# EPS_Local-Supply_Channel.net
KiCad netlist of a schematic drawn in Altium Designer
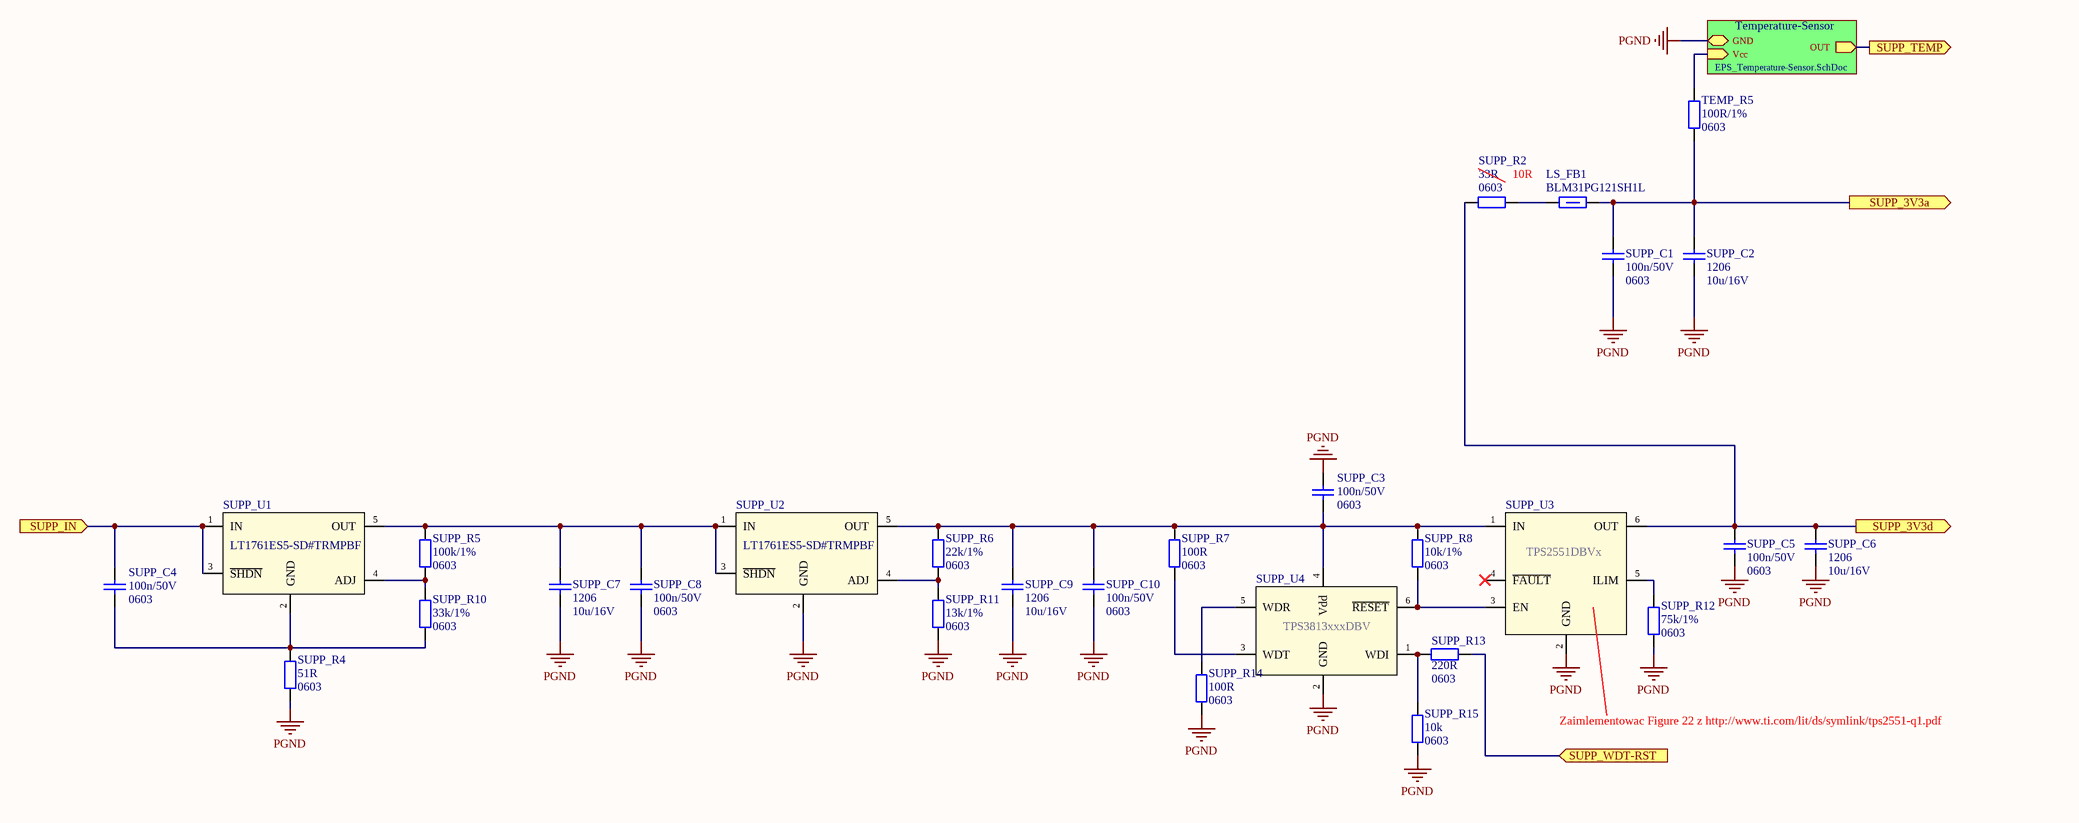
[diagram p0: EPS_Local-Supply_Channel.SchDoc]

(export (version "E")
  (design (tool "Eeschema 10.0.6"))
  (components
    (comp (ref "LS_FB1")
      (value "120R/100MHz")
      (footprint "SMD_FerriteBead_1206")
      (description "Ferrite bead, 1206, 0.02HM, 3.5A.")
      (fields (field (name "MANUFACTURER") "Murata") (field (name "MANUFACTURERPARTNUMBER") "BLM31PG121SH1L"))
      (libsource (lib "inductors") (part "BLM31PG121SH1L"))
    )
    (comp (ref "SUPP_C1")
      (value "100n/50V")
      (footprint "SMD_Capacitor_0603")
      (description "Ceramic Cap Kemet COTS 100n/50V X7R 0603")
      (fields
        (field (name "MANUFACTURER") "Kemet")
        (field (name "MANUFACTURERPARTNUMBER") "C0603T104K5RALTU")
        (field (name "PACKAGE") "0603")
      )
      (libsource (lib "capacitors") (part "Cer_C0603T104K5RALTU"))
    )
    (comp (ref "SUPP_C2")
      (value "10u/16V")
      (footprint "SMD_Capacitor_1206")
      (description "Ceramic Cap Kemet COTS 10u/16V X7R 1206")
      (fields
        (field (name "MANUFACTURERPARTNUMBER") "C1206T106K4RACTU")
        (field (name "MANUFACTURER") "Kemet")
        (field (name "PACKGE") "1206")
      )
      (libsource (lib "capacitors") (part "Cer_C1206T106K4RACTU"))
    )
    (comp (ref "SUPP_C3")
      (value "100n/50V")
      (footprint "SMD_Capacitor_0603")
      (description "Ceramic Cap Kemet COTS 100n/50V X7R 0603")
      (fields
        (field (name "MANUFACTURER") "Kemet")
        (field (name "MANUFACTURERPARTNUMBER") "C0603T104K5RALTU")
        (field (name "PACKAGE") "0603")
      )
      (libsource (lib "capacitors") (part "Cer_C0603T104K5RALTU"))
    )
    (comp (ref "SUPP_C4")
      (value "100n/50V")
      (footprint "SMD_Capacitor_0603")
      (description "Ceramic Cap Kemet COTS 100n/50V X7R 0603")
      (fields
        (field (name "MANUFACTURER") "Kemet")
        (field (name "MANUFACTURERPARTNUMBER") "C0603T104K5RALTU")
        (field (name "PACKAGE") "0603")
      )
      (libsource (lib "capacitors") (part "Cer_C0603T104K5RALTU"))
    )
    (comp (ref "SUPP_C5")
      (value "100n/50V")
      (footprint "SMD_Capacitor_0603")
      (description "Ceramic Cap Kemet COTS 100n/50V X7R 0603")
      (fields
        (field (name "MANUFACTURER") "Kemet")
        (field (name "MANUFACTURERPARTNUMBER") "C0603T104K5RALTU")
        (field (name "PACKAGE") "0603")
      )
      (libsource (lib "capacitors") (part "Cer_C0603T104K5RALTU"))
    )
    (comp (ref "SUPP_C6")
      (value "10u/16V")
      (footprint "SMD_Capacitor_1206")
      (description "Ceramic Cap Kemet COTS 10u/16V X7R 1206")
      (fields
        (field (name "MANUFACTURERPARTNUMBER") "C1206T106K4RACTU")
        (field (name "MANUFACTURER") "Kemet")
        (field (name "PACKGE") "1206")
      )
      (libsource (lib "capacitors") (part "Cer_C1206T106K4RACTU"))
    )
    (comp (ref "SUPP_C7")
      (value "10u/16V")
      (footprint "SMD_Capacitor_1206")
      (description "Ceramic Cap Kemet COTS 10u/16V X7R 1206")
      (fields
        (field (name "MANUFACTURERPARTNUMBER") "C1206T106K4RACTU")
        (field (name "MANUFACTURER") "Kemet")
        (field (name "PACKGE") "1206")
      )
      (libsource (lib "capacitors") (part "Cer_C1206T106K4RACTU"))
    )
    (comp (ref "SUPP_C8")
      (value "100n/50V")
      (footprint "SMD_Capacitor_0603")
      (description "Ceramic Cap Kemet COTS 100n/50V X7R 0603")
      (fields
        (field (name "MANUFACTURER") "Kemet")
        (field (name "MANUFACTURERPARTNUMBER") "C0603T104K5RALTU")
        (field (name "PACKAGE") "0603")
      )
      (libsource (lib "capacitors") (part "Cer_C0603T104K5RALTU"))
    )
    (comp (ref "SUPP_C9")
      (value "10u/16V")
      (footprint "SMD_Capacitor_1206")
      (description "Ceramic Cap Kemet COTS 10u/16V X7R 1206")
      (fields
        (field (name "MANUFACTURERPARTNUMBER") "C1206T106K4RACTU")
        (field (name "MANUFACTURER") "Kemet")
        (field (name "PACKGE") "1206")
      )
      (libsource (lib "capacitors") (part "Cer_C1206T106K4RACTU"))
    )
    (comp (ref "SUPP_C10")
      (value "100n/50V")
      (footprint "SMD_Capacitor_0603")
      (description "Ceramic Cap Kemet COTS 100n/50V X7R 0603")
      (fields
        (field (name "MANUFACTURER") "Kemet")
        (field (name "MANUFACTURERPARTNUMBER") "C0603T104K5RALTU")
        (field (name "PACKAGE") "0603")
      )
      (libsource (lib "capacitors") (part "Cer_C0603T104K5RALTU"))
    )
    (comp (ref "SUPP_R2")
      (value "33R")
      (footprint "SMD_Resistor_0603")
      (fields (field (name "PACKAGE") "0603"))
      (libsource (lib "") (part "Res_1"))
    )
    (comp (ref "SUPP_R4")
      (value "51R")
      (footprint "SMD_Resistor_0603")
      (fields (field (name "PACKAGE") "0603"))
      (libsource (lib "resistors") (part "Res"))
    )
    (comp (ref "SUPP_R5")
      (value "100k/1%")
      (footprint "SMD_Resistor_0603")
      (fields (field (name "PACKAGE") "0603"))
      (libsource (lib "resistors") (part "Res"))
    )
    (comp (ref "SUPP_R6")
      (value "22k/1%")
      (footprint "SMD_Resistor_0603")
      (fields (field (name "PACKAGE") "0603"))
      (libsource (lib "resistors") (part "Res"))
    )
    (comp (ref "SUPP_R7")
      (value "100R")
      (footprint "SMD_Resistor_0603")
      (fields (field (name "PACKAGE") "0603"))
      (libsource (lib "resistors") (part "Res"))
    )
    (comp (ref "SUPP_R8")
      (value "10k/1%")
      (footprint "SMD_Resistor_0603")
      (fields (field (name "PACKAGE") "0603"))
      (libsource (lib "resistors") (part "Res"))
    )
    (comp (ref "SUPP_R10")
      (value "33k/1%")
      (footprint "SMD_Resistor_0603")
      (fields (field (name "PACKAGE") "0603"))
      (libsource (lib "resistors") (part "Res"))
    )
    (comp (ref "SUPP_R11")
      (value "13k/1%")
      (footprint "SMD_Resistor_0603")
      (fields (field (name "PACKAGE") "0603"))
      (libsource (lib "resistors") (part "Res"))
    )
    (comp (ref "SUPP_R12")
      (value "75k/1%")
      (footprint "SMD_Resistor_0603")
      (fields (field (name "PACKAGE") "0603"))
      (libsource (lib "resistors") (part "Res"))
    )
    (comp (ref "SUPP_R13")
      (value "220R")
      (footprint "SMD_Resistor_0603")
      (fields (field (name "PACKAGE") "0603"))
      (libsource (lib "") (part "Res_1"))
    )
    (comp (ref "SUPP_R14")
      (value "100R")
      (footprint "SMD_Resistor_0603")
      (fields (field (name "PACKAGE") "0603"))
      (libsource (lib "resistors") (part "Res"))
    )
    (comp (ref "SUPP_R15")
      (value "10k")
      (footprint "SMD_Resistor_0603")
      (fields (field (name "PACKAGE") "0603"))
      (libsource (lib "") (part "Res_2"))
    )
    (comp (ref "SUPP_U1")
      (value "LT1761ES5-SD#TRMPBF")
      (footprint "SOT23-5")
      (description "100mA, Regulated, Low Noise, LDO Micropower Regulator in TSOT-23")
      (fields (field (name "MANUFACTURER") "Linear Technology"))
      (libsource (lib "microcircuits") (part "LT1761ES5-SD#TRMPBF"))
    )
    (comp (ref "SUPP_U2")
      (value "LT1761ES5-SD#TRMPBF")
      (footprint "SOT23-5")
      (description "100mA, Regulated, Low Noise, LDO Micropower Regulator in TSOT-23")
      (fields (field (name "MANUFACTURER") "Linear Technology"))
      (libsource (lib "microcircuits") (part "LT1761ES5-SD#TRMPBF"))
    )
    (comp (ref "SUPP_U3")
      (value "TPS2551DBVx")
      (footprint "SOT23-6")
      (description "Adjustable Current-Limited Power-Distribution Switch.")
      (fields (field (name "MANUFACTURER") "Texas Instruments"))
      (libsource (lib "microcircuits") (part "TPS2551DBVx"))
    )
    (comp (ref "SUPP_U4")
      (value "TPS3813xxxDBV")
      (footprint "SOT23-6")
      (description "Processor Supervisory Circuits with Window-Watchdog.")
      (fields (field (name "MANUFACTURER") "Texas Instruments"))
      (libsource (lib "microcircuits") (part "TPS3813xxxDBV"))
    )
    (comp (ref "TEMP_R5")
      (value "100R/1%")
      (footprint "SMD_Resistor_0603")
      (description "1k/1% Vishay CRCW 0603 Resistor. 100mW, 100ppm, 75V.")
      (fields
        (field (name "MANUFACTURER") "Vishay")
        (field (name "MANUFACTURERPARTNUMBER") "CRCW06031K00FKxxxx")
        (field (name "PACKAGE") "0603")
      )
      (libsource (lib "resistors") (part "CRCW06031K00FKxxxx"))
    )
  )
  (nets
    (net (code "1") (name "/SUPP_3V3a") (class "Default")
      (node (ref "LS_FB1") (pin "2") (pinfunction "2_2") (pintype "passive"))
      (node (ref "SUPP_C1") (pin "1") (pinfunction "1_1") (pintype "passive"))
      (node (ref "SUPP_C2") (pin "1") (pinfunction "1_1") (pintype "passive"))
      (node (ref "TEMP_R5") (pin "2") (pinfunction "2_2") (pintype "passive"))
    )
    (net (code "2") (name "/SUPP_3V3d") (class "Default")
      (node (ref "SUPP_C5") (pin "1") (pinfunction "1_1") (pintype "passive"))
      (node (ref "SUPP_C6") (pin "1") (pinfunction "1_1") (pintype "passive"))
      (node (ref "SUPP_R2") (pin "1") (pinfunction "1_1") (pintype "passive"))
      (node (ref "SUPP_U3") (pin "6") (pinfunction "OUT_6") (pintype "passive"))
    )
    (net (code "3") (name "/SUPP_IN") (class "Default")
      (node (ref "SUPP_C4") (pin "1") (pinfunction "1_1") (pintype "passive"))
      (node (ref "SUPP_U1") (pin "1") (pinfunction "IN_1") (pintype "passive"))
      (node (ref "SUPP_U1") (pin "3") (pinfunction "~{SHDN}_3") (pintype "passive"))
    )
    (net (code "5") (name "/SUPP_WDT-RST") (class "Default")
      (node (ref "SUPP_R13") (pin "2") (pinfunction "2_2") (pintype "passive"))
    )
    (net (code "6") (name "/Vcc") (class "Default")
      (node (ref "TEMP_R5") (pin "1") (pinfunction "1_1") (pintype "passive"))
    )
    (net (code "7") (name "Net-(LS_FB1-Pad1)") (class "Default")
      (node (ref "LS_FB1") (pin "1") (pinfunction "1_1") (pintype "passive"))
      (node (ref "SUPP_R2") (pin "2") (pinfunction "2_2") (pintype "passive"))
    )
    (net (code "8") (name "Net-(SUPP_U1-ADJ)") (class "Default")
      (node (ref "SUPP_R10") (pin "1") (pinfunction "1_1") (pintype "passive"))
      (node (ref "SUPP_R5") (pin "2") (pinfunction "2_2") (pintype "passive"))
      (node (ref "SUPP_U1") (pin "4") (pinfunction "ADJ_4") (pintype "passive"))
    )
    (net (code "9") (name "Net-(SUPP_U1-GND)") (class "Default")
      (node (ref "SUPP_C4") (pin "2") (pinfunction "2_2") (pintype "passive"))
      (node (ref "SUPP_R10") (pin "2") (pinfunction "2_2") (pintype "passive"))
      (node (ref "SUPP_R4") (pin "1") (pinfunction "1_1") (pintype "passive"))
      (node (ref "SUPP_U1") (pin "2") (pinfunction "GND_2") (pintype "passive"))
    )
    (net (code "10") (name "Net-(SUPP_U1-OUT)") (class "Default")
      (node (ref "SUPP_C7") (pin "1") (pinfunction "1_1") (pintype "passive"))
      (node (ref "SUPP_C8") (pin "1") (pinfunction "1_1") (pintype "passive"))
      (node (ref "SUPP_R5") (pin "1") (pinfunction "1_1") (pintype "passive"))
      (node (ref "SUPP_U1") (pin "5") (pinfunction "OUT_5") (pintype "passive"))
      (node (ref "SUPP_U2") (pin "1") (pinfunction "IN_1") (pintype "passive"))
      (node (ref "SUPP_U2") (pin "3") (pinfunction "~{SHDN}_3") (pintype "passive"))
    )
    (net (code "11") (name "Net-(SUPP_U2-ADJ)") (class "Default")
      (node (ref "SUPP_R11") (pin "1") (pinfunction "1_1") (pintype "passive"))
      (node (ref "SUPP_R6") (pin "2") (pinfunction "2_2") (pintype "passive"))
      (node (ref "SUPP_U2") (pin "4") (pinfunction "ADJ_4") (pintype "passive"))
    )
    (net (code "12") (name "Net-(SUPP_U2-OUT)") (class "Default")
      (node (ref "SUPP_C10") (pin "1") (pinfunction "1_1") (pintype "passive"))
      (node (ref "SUPP_C3") (pin "2") (pinfunction "2_2") (pintype "passive"))
      (node (ref "SUPP_C9") (pin "1") (pinfunction "1_1") (pintype "passive"))
      (node (ref "SUPP_R6") (pin "1") (pinfunction "1_1") (pintype "passive"))
      (node (ref "SUPP_R7") (pin "1") (pinfunction "1_1") (pintype "passive"))
      (node (ref "SUPP_R8") (pin "1") (pinfunction "1_1") (pintype "passive"))
      (node (ref "SUPP_U2") (pin "5") (pinfunction "OUT_5") (pintype "passive"))
      (node (ref "SUPP_U3") (pin "1") (pinfunction "IN_1") (pintype "passive"))
      (node (ref "SUPP_U4") (pin "4") (pinfunction "Vdd_4") (pintype "passive"))
    )
    (net (code "13") (name "Net-(SUPP_U3-EN)") (class "Default")
      (node (ref "SUPP_R8") (pin "2") (pinfunction "2_2") (pintype "passive"))
      (node (ref "SUPP_U3") (pin "3") (pinfunction "EN_3") (pintype "passive"))
      (node (ref "SUPP_U4") (pin "6") (pinfunction "~{RESET}_6") (pintype "passive"))
    )
    (net (code "14") (name "Net-(SUPP_U3-ILIM)") (class "Default")
      (node (ref "SUPP_R12") (pin "1") (pinfunction "1_1") (pintype "passive"))
      (node (ref "SUPP_U3") (pin "5") (pinfunction "ILIM_5") (pintype "passive"))
    )
    (net (code "15") (name "Net-(SUPP_U4-WDI)") (class "Default")
      (node (ref "SUPP_R13") (pin "1") (pinfunction "1_1") (pintype "passive"))
      (node (ref "SUPP_R15") (pin "2") (pinfunction "2_2") (pintype "passive"))
      (node (ref "SUPP_U4") (pin "1") (pinfunction "WDI_1") (pintype "passive"))
    )
    (net (code "16") (name "Net-(SUPP_U4-WDR)") (class "Default")
      (node (ref "SUPP_R14") (pin "1") (pinfunction "1_1") (pintype "passive"))
      (node (ref "SUPP_U4") (pin "5") (pinfunction "WDR_5") (pintype "passive"))
    )
    (net (code "17") (name "Net-(SUPP_U4-WDT)") (class "Default")
      (node (ref "SUPP_R7") (pin "2") (pinfunction "2_2") (pintype "passive"))
      (node (ref "SUPP_U4") (pin "3") (pinfunction "WDT_3") (pintype "passive"))
    )
    (net (code "18") (name "PGND") (class "Default")
      (node (ref "SUPP_C1") (pin "2") (pinfunction "2_2") (pintype "passive"))
      (node (ref "SUPP_C10") (pin "2") (pinfunction "2_2") (pintype "passive"))
      (node (ref "SUPP_C2") (pin "2") (pinfunction "2_2") (pintype "passive"))
      (node (ref "SUPP_C3") (pin "1") (pinfunction "1_1") (pintype "passive"))
      (node (ref "SUPP_C5") (pin "2") (pinfunction "2_2") (pintype "passive"))
      (node (ref "SUPP_C6") (pin "2") (pinfunction "2_2") (pintype "passive"))
      (node (ref "SUPP_C7") (pin "2") (pinfunction "2_2") (pintype "passive"))
      (node (ref "SUPP_C8") (pin "2") (pinfunction "2_2") (pintype "passive"))
      (node (ref "SUPP_C9") (pin "2") (pinfunction "2_2") (pintype "passive"))
      (node (ref "SUPP_R11") (pin "2") (pinfunction "2_2") (pintype "passive"))
      (node (ref "SUPP_R12") (pin "2") (pinfunction "2_2") (pintype "passive"))
      (node (ref "SUPP_R14") (pin "2") (pinfunction "2_2") (pintype "passive"))
      (node (ref "SUPP_R15") (pin "1") (pinfunction "1_1") (pintype "passive"))
      (node (ref "SUPP_R4") (pin "2") (pinfunction "2_2") (pintype "passive"))
      (node (ref "SUPP_U2") (pin "2") (pinfunction "GND_2") (pintype "passive"))
      (node (ref "SUPP_U3") (pin "2") (pinfunction "GND_2") (pintype "passive"))
      (node (ref "SUPP_U4") (pin "2") (pinfunction "GND_2") (pintype "passive"))
    )
    (net (code "19") (name "unconnected-(SUPP_U3-~{FAULT}-Pad4)") (class "Default")
      (node (ref "SUPP_U3") (pin "4") (pinfunction "~{FAULT}_4") (pintype "passive+no_connect"))
    )
  )
)
